# random-keypad-door-controller-flanged-v0.net
KiCad netlist of a schematic drawn in EAGLE
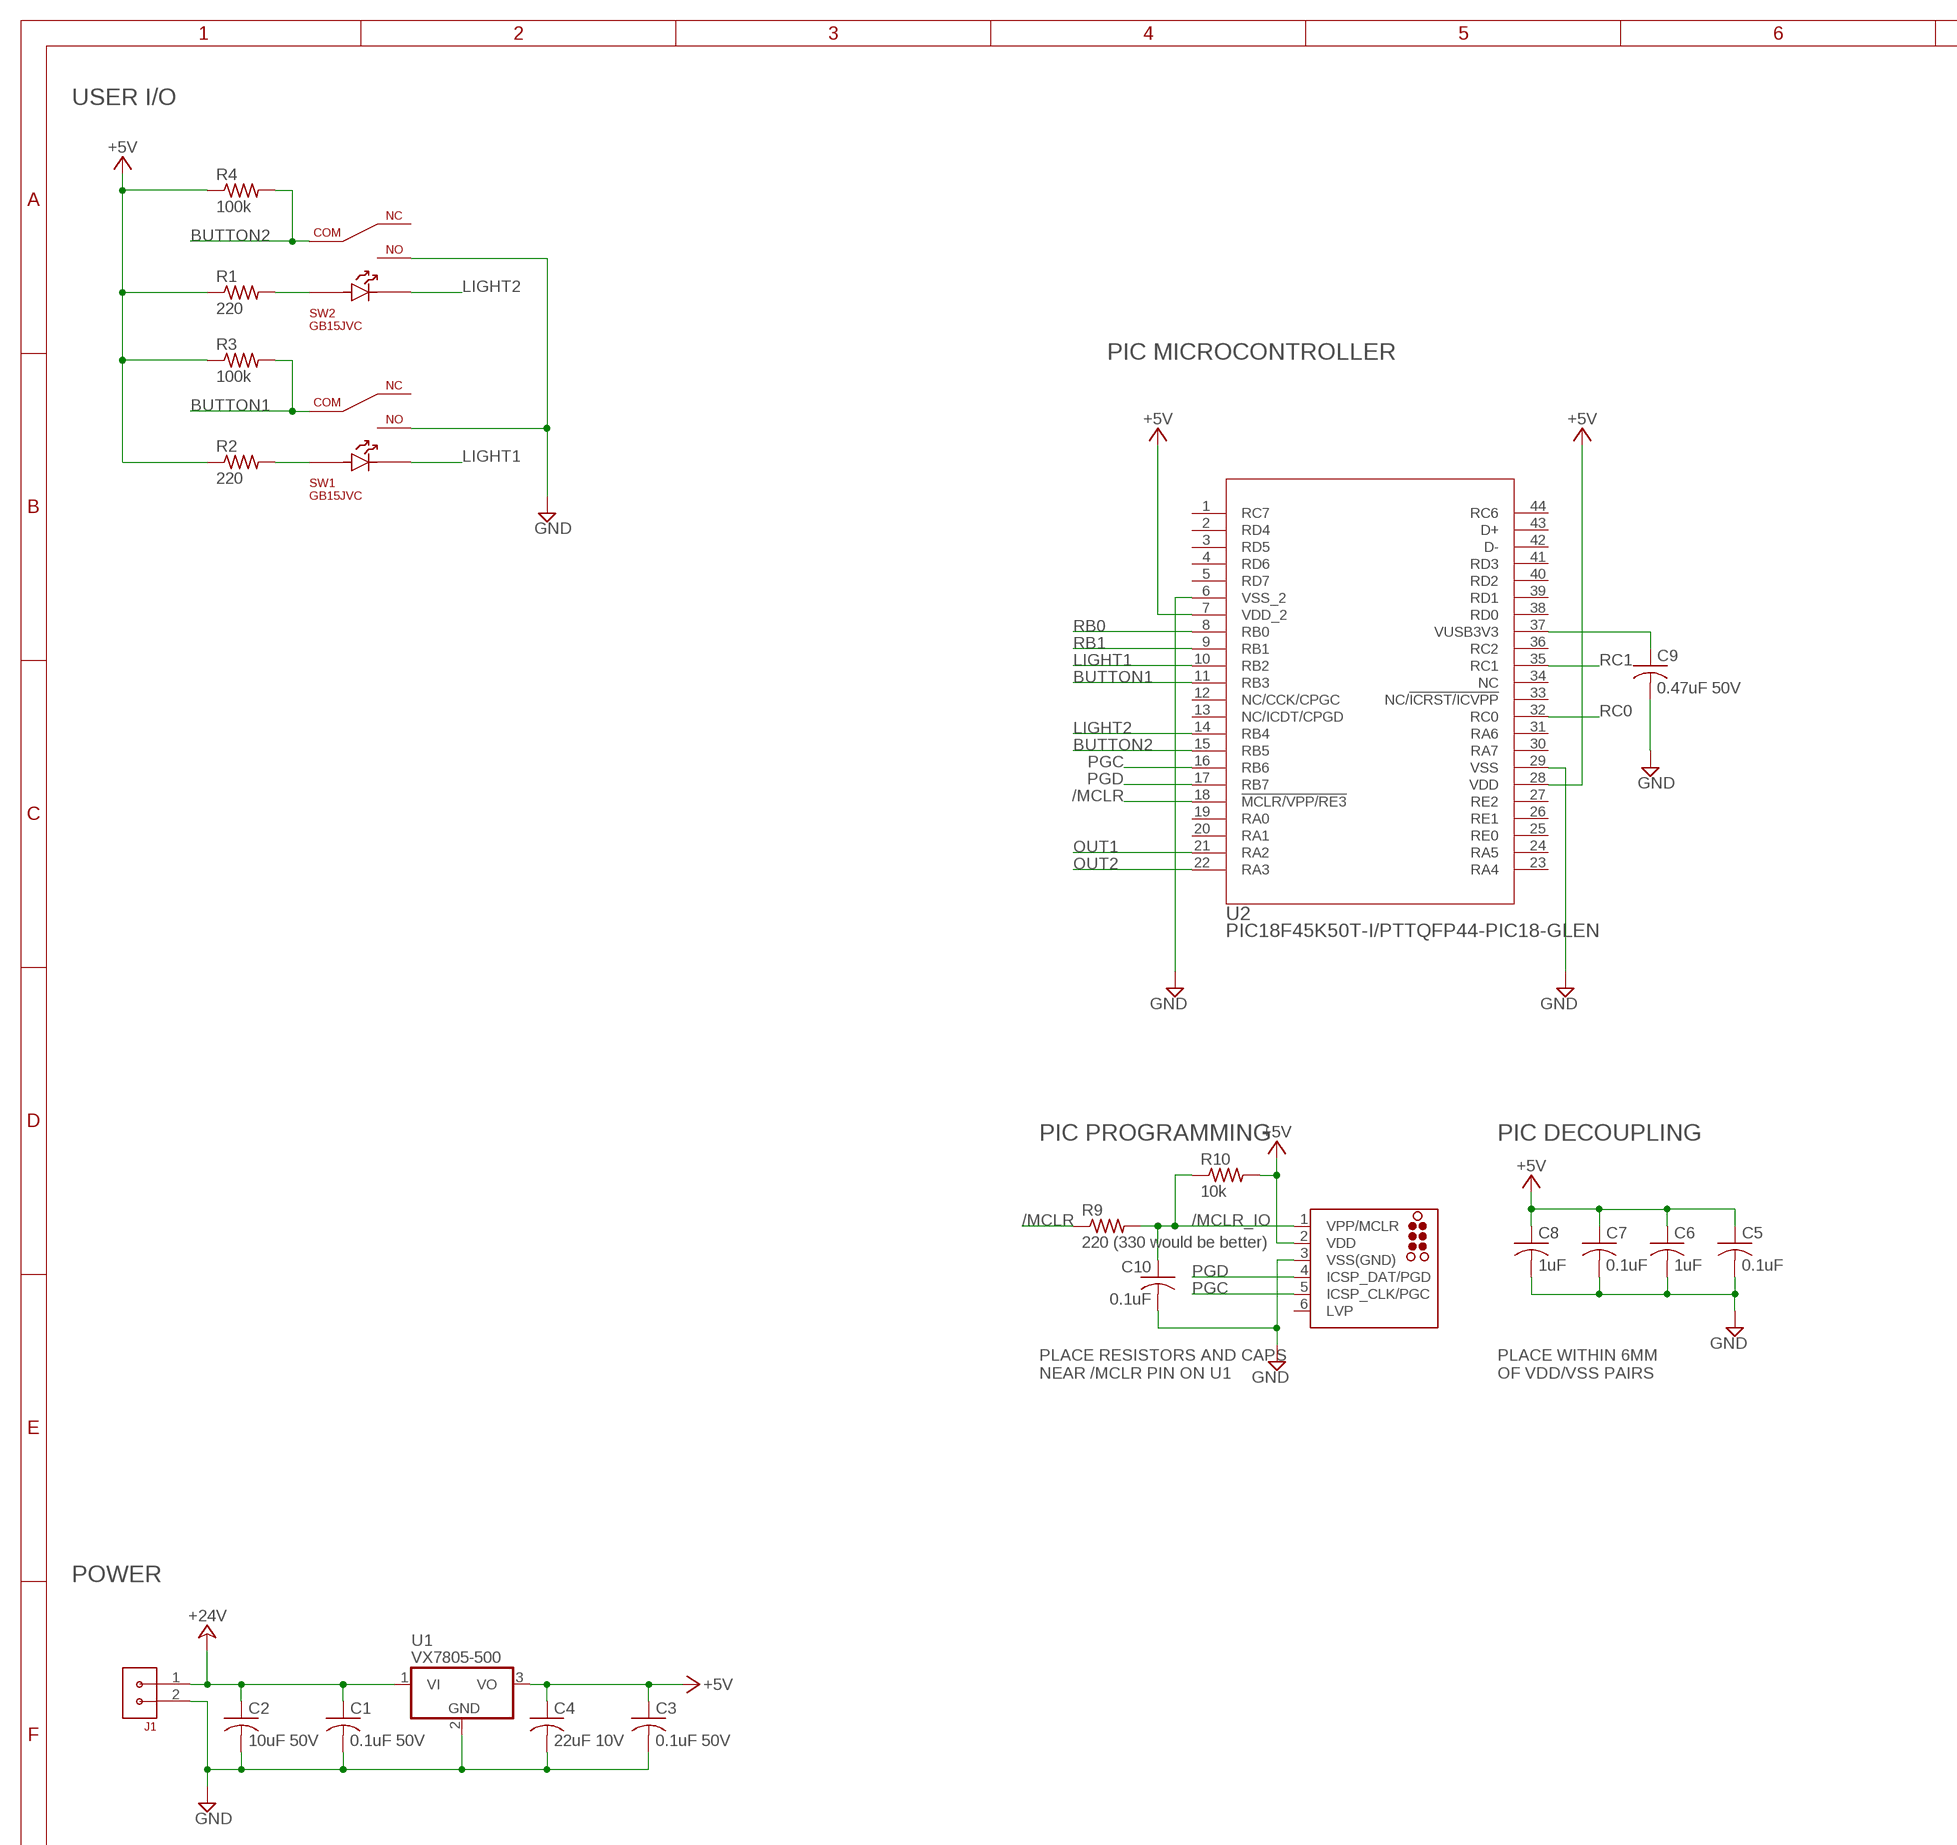
[diagram p0: schematic, sheet 1, part 1 of 2]
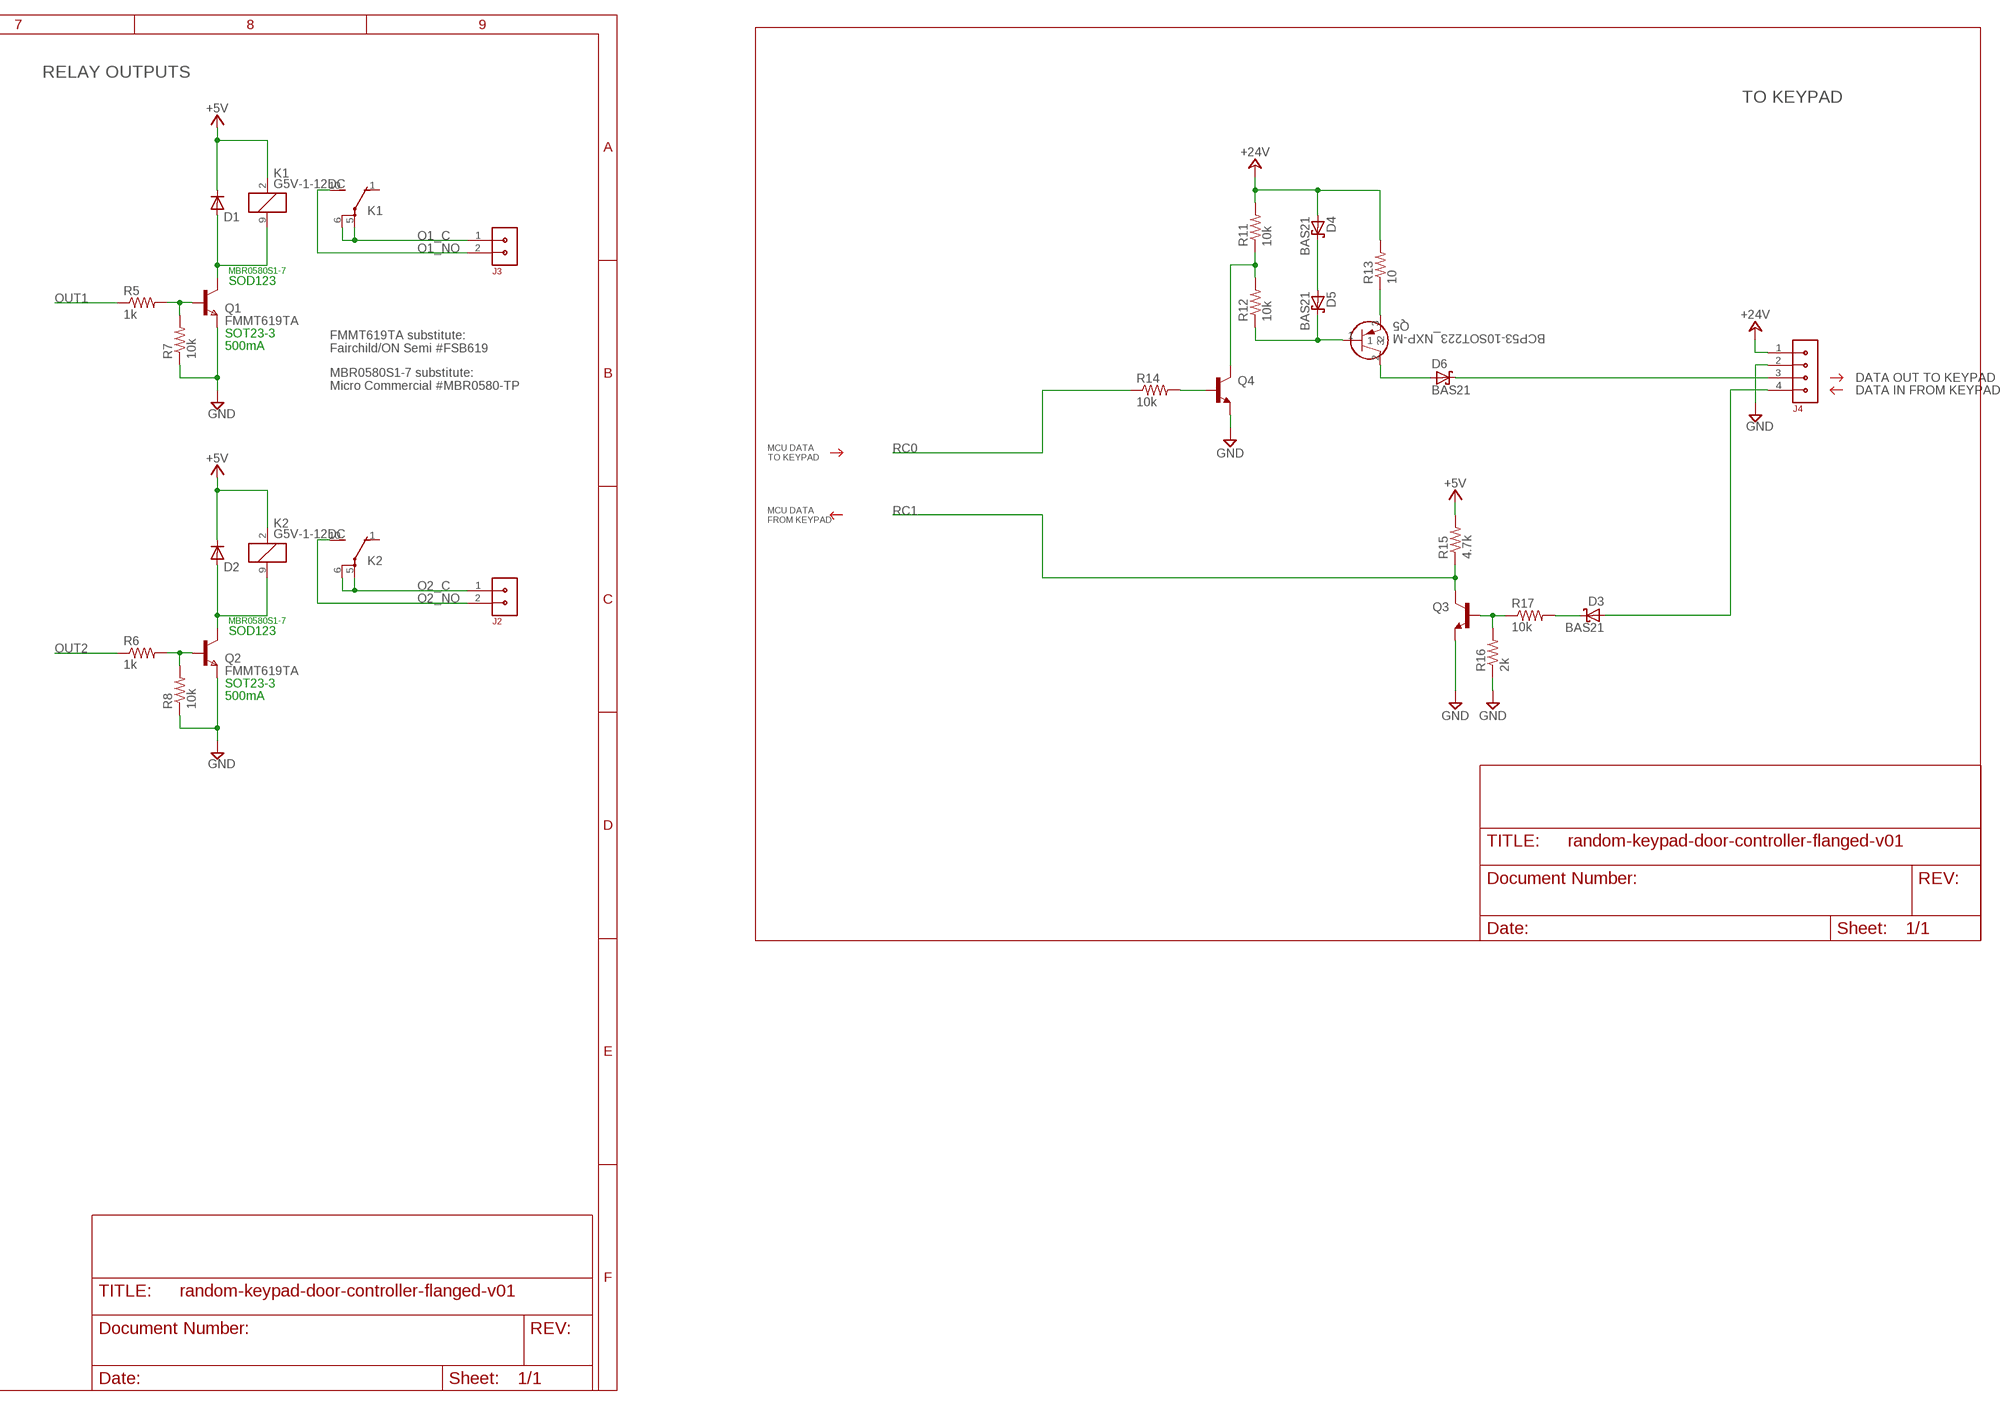
[diagram p1: schematic, sheet 1, part 2 of 2]

(export (version "E")
  (design (tool "Eeschema 10.0.6"))
  (components
    (comp (ref "C1")
      (value "0.1uF 50V")
      (footprint "eagle-import:C1206K")
      (fields (field (name "MFR") "KEMET") (field (name "MFR_PART_NO") "C1206S104M5RACTU"))
      (libsource (lib "eagle-import") (part "C-USC1206K"))
    )
    (comp (ref "C2")
      (value "10uF 50V")
      (footprint "eagle-import:C1210K")
      (fields (field (name "MFR") "KEMET") (field (name "MFR_PART_NO") "C1210C106K5RACTU"))
      (libsource (lib "eagle-import") (part "C-USC1210K"))
    )
    (comp (ref "C3")
      (value "0.1uF 50V")
      (footprint "eagle-import:C1206K")
      (fields (field (name "MFR") "KEMET") (field (name "MFR_PART_NO") "C1206S104M5RACTU"))
      (libsource (lib "eagle-import") (part "C-USC1206K"))
    )
    (comp (ref "C4")
      (value "22uF 10V")
      (footprint "eagle-import:C1206K")
      (fields (field (name "MFR") "KEMET") (field (name "MFR_PART_NO") "C1206C226K8RAC7800"))
      (libsource (lib "eagle-import") (part "C-USC1206K"))
    )
    (comp (ref "C5")
      (value "0.1uF")
      (footprint "eagle-import:C0603K")
      (libsource (lib "eagle-import") (part "C-USC0603K"))
    )
    (comp (ref "C6")
      (value "1uF")
      (footprint "eagle-import:C0603K")
      (libsource (lib "eagle-import") (part "C-USC0603K"))
    )
    (comp (ref "C7")
      (value "0.1uF")
      (footprint "eagle-import:C0603K")
      (libsource (lib "eagle-import") (part "C-USC0603K"))
    )
    (comp (ref "C8")
      (value "1uF")
      (footprint "eagle-import:C0603K")
      (libsource (lib "eagle-import") (part "C-USC0603K"))
    )
    (comp (ref "C9")
      (value "0.47uF 50V")
      (footprint "eagle-import:C1206K")
      (fields (field (name "MFR") "KEMET") (field (name "MFR_PART_NO") "C1206C474K5RACTU"))
      (libsource (lib "eagle-import") (part "C-USC1206K"))
    )
    (comp (ref "C10")
      (value "0.1uF")
      (footprint "eagle-import:C0603K")
      (libsource (lib "eagle-import") (part "C-USC0603K"))
    )
    (comp (ref "D1")
      (value "1N4148W-TP")
      (footprint "eagle-import:SOD123")
      (fields (field (name "MFR") "DIODES INC") (field (name "MFR_PART_NO") "MBR0580S1-7"))
      (libsource (lib "eagle-import") (part "DIODE-SOD123"))
    )
    (comp (ref "D2")
      (value "1N4148W-TP")
      (footprint "eagle-import:SOD123")
      (fields (field (name "MFR") "DIODES INC") (field (name "MFR_PART_NO") "MBR0580S1-7"))
      (libsource (lib "eagle-import") (part "DIODE-SOD123"))
    )
    (comp (ref "D3")
      (value "BAS21")
      (footprint "eagle-import:SOT23")
      (libsource (lib "eagle-import") (part "BAS40"))
    )
    (comp (ref "D4")
      (value "BAS21")
      (footprint "eagle-import:SOT23")
      (libsource (lib "eagle-import") (part "BAS40"))
    )
    (comp (ref "D5")
      (value "BAS21")
      (footprint "eagle-import:SOT23")
      (libsource (lib "eagle-import") (part "BAS40"))
    )
    (comp (ref "D6")
      (value "BAS21")
      (footprint "eagle-import:SOT23")
      (libsource (lib "eagle-import") (part "BAS40"))
    )
    (comp (ref "DEBUG")
      (value "TC2030-MCP-NL")
      (footprint "eagle-import:TC2030-MCP-NL")
      (libsource (lib "eagle-import") (part "TC2030-MCP-NL"))
    )
    (comp (ref "J1")
      (value "CON-3.81MM-1X2-PHOENIX")
      (footprint "eagle-import:CON-PHOENIX-3.81-1X2-RA")
      (libsource (lib "eagle-import") (part "CON-3.81MM-1X2-PHOENIX"))
    )
    (comp (ref "J2")
      (value "CON-3.81MM-1X2-PHOENIX")
      (footprint "eagle-import:CON-PHOENIX-3.81-1X2-RA")
      (libsource (lib "eagle-import") (part "CON-3.81MM-1X2-PHOENIX"))
    )
    (comp (ref "J3")
      (value "CON-3.81MM-1X2-PHOENIX")
      (footprint "eagle-import:CON-PHOENIX-3.81-1X2-RA")
      (libsource (lib "eagle-import") (part "CON-3.81MM-1X2-PHOENIX"))
    )
    (comp (ref "J4")
      (value "CON-3.81MM-1X4-PHOENIX-1803293")
      (footprint "eagle-import:CON-PHOENIX-1803293-3.81-1X4")
      (libsource (lib "eagle-import") (part "CON-3.81MM-1X4-PHOENIX-1803293"))
    )
    (comp (ref "K1")
      (value "G5V-1-12DC")
      (footprint "eagle-import:G5V1")
      (fields
        (field (name "MPN") "G5V-1-DC24")
        (field (name "MFR") "OMRON")
        (field (name "MFR_PART_NO") "G5V-1-DC5")
      )
      (libsource (lib "eagle-import") (part "G5V1"))
    )
    (comp (ref "K2")
      (value "G5V-1-12DC")
      (footprint "eagle-import:G5V1")
      (fields
        (field (name "MPN") "G5V-1-DC24")
        (field (name "MFR") "OMRON")
        (field (name "MFR_PART_NO") "G5V-1-DC5")
      )
      (libsource (lib "eagle-import") (part "G5V1"))
    )
    (comp (ref "Q1")
      (value "FMMT619TA")
      (footprint "eagle-import:SOT-23")
      (fields (field (name "MPN") "DSS20201L-7") (field (name "MFR") "DIODES INC"))
      (libsource (lib "eagle-import") (part "NPNSOT23"))
    )
    (comp (ref "Q2")
      (value "FMMT619TA")
      (footprint "eagle-import:SOT-23")
      (fields (field (name "MPN") "DSS20201L-7") (field (name "MFR") "DIODES INC"))
      (libsource (lib "eagle-import") (part "NPNSOT23"))
    )
    (comp (ref "Q3")
      (value "BC817-40-NPN-SOT23-BEC")
      (footprint "eagle-import:SOT23-BEC")
      (libsource (lib "eagle-import") (part "-NPN-SOT23-BECBC817-40"))
    )
    (comp (ref "Q4")
      (value "BC817-40-NPN-SOT23-BEC")
      (footprint "eagle-import:SOT23-BEC")
      (libsource (lib "eagle-import") (part "-NPN-SOT23-BECBC817-40"))
    )
    (comp (ref "Q5")
      (value "BCP53-10SOT223_NXP-M")
      (footprint "eagle-import:SOT223_NXP-M")
      (fields
        (field (name "MANUFACTURER_PART_NUMBER") "BCP53-10")
        (field (name "COPYRIGHT") "Copyright (C) 2021 Ultra Librarian. All rights reserved.")
      )
      (libsource (lib "eagle-import") (part "BCP53-10SOT223_NXP-M"))
    )
    (comp (ref "R1")
      (value "220")
      (footprint "eagle-import:R0603")
      (libsource (lib "eagle-import") (part "R-US_R0603"))
    )
    (comp (ref "R2")
      (value "220")
      (footprint "eagle-import:R0603")
      (libsource (lib "eagle-import") (part "R-US_R0603"))
    )
    (comp (ref "R3")
      (value "100k")
      (footprint "eagle-import:R0603")
      (libsource (lib "eagle-import") (part "R-US_R0603"))
    )
    (comp (ref "R4")
      (value "100k")
      (footprint "eagle-import:R0603")
      (libsource (lib "eagle-import") (part "R-US_R0603"))
    )
    (comp (ref "R5")
      (value "1k")
      (footprint "eagle-import:R0603")
      (fields (field (name "MFR") "BOURNS") (field (name "MFR_PART_NO") "CR1206-JW-102ELF"))
      (libsource (lib "eagle-import") (part "R-US_R0603"))
    )
    (comp (ref "R6")
      (value "1k")
      (footprint "eagle-import:R0603")
      (fields (field (name "MFR") "BOURNS") (field (name "MFR_PART_NO") "CR1206-JW-102ELF"))
      (libsource (lib "eagle-import") (part "R-US_R0603"))
    )
    (comp (ref "R7")
      (value "10k")
      (footprint "eagle-import:R0603")
      (fields (field (name "MFR") "BOURNS") (field (name "MFR_PART_NO") "CR1206-JW-102ELF"))
      (libsource (lib "eagle-import") (part "R-US_R0603"))
    )
    (comp (ref "R8")
      (value "10k")
      (footprint "eagle-import:R0603")
      (fields (field (name "MFR") "BOURNS") (field (name "MFR_PART_NO") "CR1206-JW-102ELF"))
      (libsource (lib "eagle-import") (part "R-US_R0603"))
    )
    (comp (ref "R9")
      (value "220 (330 would be better)")
      (footprint "eagle-import:R0603")
      (libsource (lib "eagle-import") (part "R-US_R0603"))
    )
    (comp (ref "R10")
      (value "10k")
      (footprint "eagle-import:R0603")
      (libsource (lib "eagle-import") (part "R-US_R0603"))
    )
    (comp (ref "R11")
      (value "10k")
      (footprint "eagle-import:R0603")
      (libsource (lib "eagle-import") (part "resistor_R-US_R0603"))
    )
    (comp (ref "R12")
      (value "10k")
      (footprint "eagle-import:R0603")
      (libsource (lib "eagle-import") (part "resistor_R-US_R0603"))
    )
    (comp (ref "R13")
      (value "10")
      (footprint "eagle-import:R0603")
      (libsource (lib "eagle-import") (part "resistor_R-US_R0603"))
    )
    (comp (ref "R14")
      (value "10k")
      (footprint "eagle-import:R0603")
      (libsource (lib "eagle-import") (part "resistor_R-US_R0603"))
    )
    (comp (ref "R15")
      (value "4.7k")
      (footprint "eagle-import:R0603")
      (libsource (lib "eagle-import") (part "resistor_R-US_R0603"))
    )
    (comp (ref "R16")
      (value "2k")
      (footprint "eagle-import:R0603")
      (libsource (lib "eagle-import") (part "resistor_R-US_R0603"))
    )
    (comp (ref "R17")
      (value "10k")
      (footprint "eagle-import:R0603")
      (libsource (lib "eagle-import") (part "resistor_R-US_R0603"))
    )
    (comp (ref "SW1")
      (value "GB15JVC")
      (footprint "eagle-import:GB15JHC")
      (libsource (lib "eagle-import") (part "GB15JHC"))
    )
    (comp (ref "SW2")
      (value "GB15JVC")
      (footprint "eagle-import:GB15JHC")
      (libsource (lib "eagle-import") (part "GB15JHC"))
    )
    (comp (ref "U1")
      (value "VX7805-500")
      (footprint "eagle-import:CUI-78XX-500")
      (libsource (lib "eagle-import") (part "CUI-V7803-500"))
    )
    (comp (ref "U2")
      (value "PIC18F45K50T-I/PTTQFP44-PIC18-GLEN")
      (footprint "eagle-import:TQFP44-PIC18-GLEN")
      (libsource (lib "eagle-import") (part "PIC18F45K50T-I/PTTQFP44-PIC18-GLEN"))
    )
  )
  (nets
    (net (code "1") (name "+5V") (class "Default")
      (node (ref "C3") (pin "1") (pinfunction "1_1") (pintype "passive"))
      (node (ref "C4") (pin "1") (pinfunction "1_1") (pintype "passive"))
      (node (ref "C5") (pin "1") (pinfunction "1_1") (pintype "passive"))
      (node (ref "C6") (pin "1") (pinfunction "1_1") (pintype "passive"))
      (node (ref "C7") (pin "1") (pinfunction "1_1") (pintype "passive"))
      (node (ref "C8") (pin "1") (pinfunction "1_1") (pintype "passive"))
      (node (ref "D1") (pin "C") (pinfunction "C_C") (pintype "passive"))
      (node (ref "D2") (pin "C") (pinfunction "C_C") (pintype "passive"))
      (node (ref "DEBUG") (pin "2") (pinfunction "VDD_2") (pintype "power_in"))
      (node (ref "K1") (pin "2") (pinfunction "1_2") (pintype "passive"))
      (node (ref "K2") (pin "2") (pinfunction "1_2") (pintype "passive"))
      (node (ref "R1") (pin "1") (pinfunction "1_1") (pintype "passive"))
      (node (ref "R10") (pin "2") (pinfunction "2_2") (pintype "passive"))
      (node (ref "R15") (pin "2") (pinfunction "2_2") (pintype "passive"))
      (node (ref "R2") (pin "1") (pinfunction "1_1") (pintype "passive"))
      (node (ref "R3") (pin "1") (pinfunction "1_1") (pintype "passive"))
      (node (ref "R4") (pin "1") (pinfunction "1_1") (pintype "passive"))
      (node (ref "U1") (pin "3") (pinfunction "VO_3") (pintype "passive"))
      (node (ref "U2") (pin "28") (pinfunction "VDD_28") (pintype "power_in"))
      (node (ref "U2") (pin "7") (pinfunction "VDD_2_7") (pintype "power_in"))
    )
    (net (code "2") (name "+24V") (class "Default")
      (node (ref "C1") (pin "1") (pinfunction "1_1") (pintype "passive"))
      (node (ref "C2") (pin "1") (pinfunction "1_1") (pintype "passive"))
      (node (ref "D4") (pin "1") (pinfunction "A_1") (pintype "passive"))
      (node (ref "J1") (pin "1") (pinfunction "1_1") (pintype "bidirectional"))
      (node (ref "J4") (pin "1") (pinfunction "1_1") (pintype "bidirectional"))
      (node (ref "R11") (pin "2") (pinfunction "2_2") (pintype "passive"))
      (node (ref "R13") (pin "2") (pinfunction "2_2") (pintype "passive"))
      (node (ref "U1") (pin "1") (pinfunction "VI_1") (pintype "input"))
    )
    (net (code "3") (name "/BUTTON1") (class "Default")
      (node (ref "R3") (pin "2") (pinfunction "2_2") (pintype "passive"))
      (node (ref "SW1") (pin "5") (pinfunction "5_5") (pintype "bidirectional"))
      (node (ref "U2") (pin "11") (pinfunction "RB3_11") (pintype "bidirectional"))
    )
    (net (code "4") (name "/BUTTON2") (class "Default")
      (node (ref "R4") (pin "2") (pinfunction "2_2") (pintype "passive"))
      (node (ref "SW2") (pin "5") (pinfunction "5_5") (pintype "bidirectional"))
      (node (ref "U2") (pin "15") (pinfunction "RB5_15") (pintype "bidirectional"))
    )
    (net (code "5") (name "/LIGHT1") (class "Default")
      (node (ref "SW1") (pin "3") (pinfunction "3_3") (pintype "bidirectional"))
      (node (ref "U2") (pin "10") (pinfunction "RB2_10") (pintype "bidirectional"))
    )
    (net (code "6") (name "/LIGHT2") (class "Default")
      (node (ref "SW2") (pin "3") (pinfunction "3_3") (pintype "bidirectional"))
      (node (ref "U2") (pin "14") (pinfunction "RB4_14") (pintype "bidirectional"))
    )
    (net (code "7") (name "/O1_C") (class "Default")
      (node (ref "J3") (pin "1") (pinfunction "1_1") (pintype "bidirectional"))
      (node (ref "K1") (pin "5") (pinfunction "P_5") (pintype "passive"))
      (node (ref "K1") (pin "6") (pinfunction "P_6") (pintype "passive"))
    )
    (net (code "8") (name "/O1_NO") (class "Default")
      (node (ref "J3") (pin "2") (pinfunction "2_2") (pintype "bidirectional"))
      (node (ref "K1") (pin "10") (pinfunction "S_10") (pintype "passive"))
    )
    (net (code "9") (name "/O2_C") (class "Default")
      (node (ref "J2") (pin "1") (pinfunction "1_1") (pintype "bidirectional"))
      (node (ref "K2") (pin "5") (pinfunction "P_5") (pintype "passive"))
      (node (ref "K2") (pin "6") (pinfunction "P_6") (pintype "passive"))
    )
    (net (code "10") (name "/O2_NO") (class "Default")
      (node (ref "J2") (pin "2") (pinfunction "2_2") (pintype "bidirectional"))
      (node (ref "K2") (pin "10") (pinfunction "S_10") (pintype "passive"))
    )
    (net (code "11") (name "/OUT1") (class "Default")
      (node (ref "R5") (pin "1") (pinfunction "1_1") (pintype "passive"))
      (node (ref "U2") (pin "21") (pinfunction "RA2_21") (pintype "bidirectional"))
    )
    (net (code "12") (name "/OUT2") (class "Default")
      (node (ref "R6") (pin "1") (pinfunction "1_1") (pintype "passive"))
      (node (ref "U2") (pin "22") (pinfunction "RA3_22") (pintype "bidirectional"))
    )
    (net (code "13") (name "/PGC") (class "Default")
      (node (ref "DEBUG") (pin "5") (pinfunction "ICSP_CLK/PGC_5") (pintype "output"))
      (node (ref "U2") (pin "16") (pinfunction "RB6_16") (pintype "bidirectional"))
    )
    (net (code "14") (name "/PGD") (class "Default")
      (node (ref "DEBUG") (pin "4") (pinfunction "ICSP_DAT/PGD_4") (pintype "bidirectional"))
      (node (ref "U2") (pin "17") (pinfunction "RB7_17") (pintype "bidirectional"))
    )
    (net (code "15") (name "/RB0") (class "Default")
      (node (ref "U2") (pin "8") (pinfunction "RB0_8") (pintype "bidirectional"))
    )
    (net (code "16") (name "/RB1") (class "Default")
      (node (ref "U2") (pin "9") (pinfunction "RB1_9") (pintype "bidirectional"))
    )
    (net (code "17") (name "/RC0") (class "Default")
      (node (ref "R14") (pin "1") (pinfunction "1_1") (pintype "passive"))
      (node (ref "U2") (pin "32") (pinfunction "RC0_32") (pintype "bidirectional"))
    )
    (net (code "18") (name "/RC1") (class "Default")
      (node (ref "Q3") (pin "C") (pinfunction "C_C") (pintype "passive"))
      (node (ref "R15") (pin "1") (pinfunction "1_1") (pintype "passive"))
      (node (ref "U2") (pin "35") (pinfunction "RC1_35") (pintype "bidirectional"))
    )
    (net (code "19") (name "/{slash}MCLR") (class "Default")
      (node (ref "R9") (pin "1") (pinfunction "1_1") (pintype "passive"))
      (node (ref "U2") (pin "18") (pinfunction "~{MCLR/VPP/RE3}_18") (pintype "bidirectional"))
    )
    (net (code "20") (name "/{slash}MCLR_IO") (class "Default")
      (node (ref "C10") (pin "1") (pinfunction "1_1") (pintype "passive"))
      (node (ref "DEBUG") (pin "1") (pinfunction "VPP/MCLR_1") (pintype "passive"))
      (node (ref "R10") (pin "1") (pinfunction "1_1") (pintype "passive"))
      (node (ref "R9") (pin "2") (pinfunction "2_2") (pintype "passive"))
    )
    (net (code "21") (name "GND") (class "Default")
      (node (ref "C1") (pin "2") (pinfunction "2_2") (pintype "passive"))
      (node (ref "C10") (pin "2") (pinfunction "2_2") (pintype "passive"))
      (node (ref "C2") (pin "2") (pinfunction "2_2") (pintype "passive"))
      (node (ref "C3") (pin "2") (pinfunction "2_2") (pintype "passive"))
      (node (ref "C4") (pin "2") (pinfunction "2_2") (pintype "passive"))
      (node (ref "C5") (pin "2") (pinfunction "2_2") (pintype "passive"))
      (node (ref "C6") (pin "2") (pinfunction "2_2") (pintype "passive"))
      (node (ref "C7") (pin "2") (pinfunction "2_2") (pintype "passive"))
      (node (ref "C8") (pin "2") (pinfunction "2_2") (pintype "passive"))
      (node (ref "C9") (pin "2") (pinfunction "2_2") (pintype "passive"))
      (node (ref "DEBUG") (pin "3") (pinfunction "VSS(GND)_3") (pintype "power_in"))
      (node (ref "J1") (pin "2") (pinfunction "2_2") (pintype "bidirectional"))
      (node (ref "J4") (pin "2") (pinfunction "2_2") (pintype "bidirectional"))
      (node (ref "Q1") (pin "2") (pinfunction "E_2") (pintype "passive"))
      (node (ref "Q2") (pin "2") (pinfunction "E_2") (pintype "passive"))
      (node (ref "Q3") (pin "E") (pinfunction "E_E") (pintype "passive"))
      (node (ref "Q4") (pin "E") (pinfunction "E_E") (pintype "passive"))
      (node (ref "R16") (pin "1") (pinfunction "1_1") (pintype "passive"))
      (node (ref "R7") (pin "1") (pinfunction "1_1") (pintype "passive"))
      (node (ref "R8") (pin "1") (pinfunction "1_1") (pintype "passive"))
      (node (ref "SW1") (pin "4") (pinfunction "4_4") (pintype "bidirectional"))
      (node (ref "SW2") (pin "4") (pinfunction "4_4") (pintype "bidirectional"))
      (node (ref "U1") (pin "2") (pinfunction "GND_2") (pintype "passive"))
      (node (ref "U2") (pin "29") (pinfunction "VSS_29") (pintype "power_in"))
      (node (ref "U2") (pin "6") (pinfunction "VSS_2_6") (pintype "power_in"))
    )
    (net (code "22") (name "Net-(D3-A)") (class "Default")
      (node (ref "D3") (pin "1") (pinfunction "A_1") (pintype "passive"))
      (node (ref "J4") (pin "4") (pinfunction "4_4") (pintype "bidirectional"))
    )
    (net (code "23") (name "Net-(D3-C)") (class "Default")
      (node (ref "D3") (pin "3") (pinfunction "C_3") (pintype "passive"))
      (node (ref "R17") (pin "2") (pinfunction "2_2") (pintype "passive"))
    )
    (net (code "24") (name "Net-(D4-C)") (class "Default")
      (node (ref "D4") (pin "3") (pinfunction "C_3") (pintype "passive"))
      (node (ref "D5") (pin "1") (pinfunction "A_1") (pintype "passive"))
    )
    (net (code "25") (name "Net-(D5-C)") (class "Default")
      (node (ref "D5") (pin "3") (pinfunction "C_3") (pintype "passive"))
      (node (ref "Q5") (pin "1") (pinfunction "1_1") (pintype "passive"))
      (node (ref "R12") (pin "1") (pinfunction "1_1") (pintype "passive"))
    )
    (net (code "26") (name "Net-(D6-A)") (class "Default")
      (node (ref "D6") (pin "1") (pinfunction "A_1") (pintype "passive"))
      (node (ref "Q5") (pin "2") (pinfunction "2_2") (pintype "passive"))
    )
    (net (code "27") (name "Net-(D6-C)") (class "Default")
      (node (ref "D6") (pin "3") (pinfunction "C_3") (pintype "passive"))
      (node (ref "J4") (pin "3") (pinfunction "3_3") (pintype "bidirectional"))
    )
    (net (code "28") (name "Net-(K1A-2)") (class "Default")
      (node (ref "D1") (pin "A") (pinfunction "A_A") (pintype "passive"))
      (node (ref "K1") (pin "9") (pinfunction "2_9") (pintype "passive"))
      (node (ref "Q1") (pin "1") (pinfunction "C_1") (pintype "passive"))
    )
    (net (code "29") (name "Net-(K2A-2)") (class "Default")
      (node (ref "D2") (pin "A") (pinfunction "A_A") (pintype "passive"))
      (node (ref "K2") (pin "9") (pinfunction "2_9") (pintype "passive"))
      (node (ref "Q2") (pin "1") (pinfunction "C_1") (pintype "passive"))
    )
    (net (code "30") (name "Net-(Q1-B)") (class "Default")
      (node (ref "Q1") (pin "3") (pinfunction "B_3") (pintype "passive"))
      (node (ref "R5") (pin "2") (pinfunction "2_2") (pintype "passive"))
      (node (ref "R7") (pin "2") (pinfunction "2_2") (pintype "passive"))
    )
    (net (code "31") (name "Net-(Q2-B)") (class "Default")
      (node (ref "Q2") (pin "3") (pinfunction "B_3") (pintype "passive"))
      (node (ref "R6") (pin "2") (pinfunction "2_2") (pintype "passive"))
      (node (ref "R8") (pin "2") (pinfunction "2_2") (pintype "passive"))
    )
    (net (code "32") (name "Net-(Q3-PadB)") (class "Default")
      (node (ref "Q3") (pin "B") (pinfunction "B_B") (pintype "passive"))
      (node (ref "R16") (pin "2") (pinfunction "2_2") (pintype "passive"))
      (node (ref "R17") (pin "1") (pinfunction "1_1") (pintype "passive"))
    )
    (net (code "33") (name "Net-(Q4-PadB)") (class "Default")
      (node (ref "Q4") (pin "B") (pinfunction "B_B") (pintype "passive"))
      (node (ref "R14") (pin "2") (pinfunction "2_2") (pintype "passive"))
    )
    (net (code "34") (name "Net-(Q4-PadC)") (class "Default")
      (node (ref "Q4") (pin "C") (pinfunction "C_C") (pintype "passive"))
      (node (ref "R11") (pin "1") (pinfunction "1_1") (pintype "passive"))
      (node (ref "R12") (pin "2") (pinfunction "2_2") (pintype "passive"))
    )
    (net (code "35") (name "Net-(Q5-Pad3)") (class "Default")
      (node (ref "Q5") (pin "3") (pinfunction "3_3") (pintype "passive"))
      (node (ref "R13") (pin "1") (pinfunction "1_1") (pintype "passive"))
    )
    (net (code "36") (name "Net-(R1-Pad2)") (class "Default")
      (node (ref "R1") (pin "2") (pinfunction "2_2") (pintype "passive"))
      (node (ref "SW2") (pin "1") (pinfunction "1_1") (pintype "bidirectional"))
    )
    (net (code "37") (name "Net-(R2-Pad2)") (class "Default")
      (node (ref "R2") (pin "2") (pinfunction "2_2") (pintype "passive"))
      (node (ref "SW1") (pin "1") (pinfunction "1_1") (pintype "bidirectional"))
    )
    (net (code "38") (name "Net-(U2-VUSB3V3)") (class "Default")
      (node (ref "C9") (pin "1") (pinfunction "1_1") (pintype "passive"))
      (node (ref "U2") (pin "37") (pinfunction "VUSB3V3_37") (pintype "power_in"))
    )
    (net (code "39") (name "unconnected-(DEBUG-LVP-Pad6)") (class "Default")
      (node (ref "DEBUG") (pin "6") (pinfunction "LVP_6") (pintype "bidirectional"))
    )
    (net (code "40") (name "unconnected-(K1B-O-Pad1)") (class "Default")
      (node (ref "K1") (pin "1") (pinfunction "O_1") (pintype "passive"))
    )
    (net (code "41") (name "unconnected-(K2B-O-Pad1)") (class "Default")
      (node (ref "K2") (pin "1") (pinfunction "O_1") (pintype "passive"))
    )
    (net (code "42") (name "unconnected-(SW1-Pad6)") (class "Default")
      (node (ref "SW1") (pin "6") (pinfunction "6_6") (pintype "bidirectional"))
    )
    (net (code "43") (name "unconnected-(SW2-Pad6)") (class "Default")
      (node (ref "SW2") (pin "6") (pinfunction "6_6") (pintype "bidirectional"))
    )
    (net (code "44") (name "unconnected-(U2-D+-Pad43)") (class "Default")
      (node (ref "U2") (pin "43") (pinfunction "D+_43") (pintype "passive"))
    )
    (net (code "45") (name "unconnected-(U2-D--Pad42)") (class "Default")
      (node (ref "U2") (pin "42") (pinfunction "D-_42") (pintype "passive"))
    )
    (net (code "46") (name "unconnected-(U2-NC-Pad34)") (class "Default")
      (node (ref "U2") (pin "34") (pinfunction "NC_34") (pintype "no_connect"))
    )
    (net (code "47") (name "unconnected-(U2-NC{slash}CCK{slash}CPGC-Pad12)") (class "Default")
      (node (ref "U2") (pin "12") (pinfunction "NC/CCK/CPGC_12") (pintype "bidirectional"))
    )
    (net (code "48") (name "unconnected-(U2-NC{slash}ICDT{slash}CPGD-Pad13)") (class "Default")
      (node (ref "U2") (pin "13") (pinfunction "NC/ICDT/CPGD_13") (pintype "bidirectional"))
    )
    (net (code "49") (name "unconnected-(U2-NC{slash}~{ICRST{slash}ICVPP}-Pad33)") (class "Default")
      (node (ref "U2") (pin "33") (pinfunction "NC/~{ICRST/ICVPP}_33") (pintype "bidirectional"))
    )
    (net (code "50") (name "unconnected-(U2-RA0-Pad19)") (class "Default")
      (node (ref "U2") (pin "19") (pinfunction "RA0_19") (pintype "bidirectional"))
    )
    (net (code "51") (name "unconnected-(U2-RA1-Pad20)") (class "Default")
      (node (ref "U2") (pin "20") (pinfunction "RA1_20") (pintype "bidirectional"))
    )
    (net (code "52") (name "unconnected-(U2-RA4-Pad23)") (class "Default")
      (node (ref "U2") (pin "23") (pinfunction "RA4_23") (pintype "bidirectional"))
    )
    (net (code "53") (name "unconnected-(U2-RA5-Pad24)") (class "Default")
      (node (ref "U2") (pin "24") (pinfunction "RA5_24") (pintype "bidirectional"))
    )
    (net (code "54") (name "unconnected-(U2-RA6-Pad31)") (class "Default")
      (node (ref "U2") (pin "31") (pinfunction "RA6_31") (pintype "bidirectional"))
    )
    (net (code "55") (name "unconnected-(U2-RA7-Pad30)") (class "Default")
      (node (ref "U2") (pin "30") (pinfunction "RA7_30") (pintype "bidirectional"))
    )
    (net (code "56") (name "unconnected-(U2-RC2-Pad36)") (class "Default")
      (node (ref "U2") (pin "36") (pinfunction "RC2_36") (pintype "bidirectional"))
    )
    (net (code "57") (name "unconnected-(U2-RC6-Pad44)") (class "Default")
      (node (ref "U2") (pin "44") (pinfunction "RC6_44") (pintype "bidirectional"))
    )
    (net (code "58") (name "unconnected-(U2-RC7-Pad1)") (class "Default")
      (node (ref "U2") (pin "1") (pinfunction "RC7_1") (pintype "bidirectional"))
    )
    (net (code "59") (name "unconnected-(U2-RD0-Pad38)") (class "Default")
      (node (ref "U2") (pin "38") (pinfunction "RD0_38") (pintype "bidirectional"))
    )
    (net (code "60") (name "unconnected-(U2-RD1-Pad39)") (class "Default")
      (node (ref "U2") (pin "39") (pinfunction "RD1_39") (pintype "bidirectional"))
    )
    (net (code "61") (name "unconnected-(U2-RD2-Pad40)") (class "Default")
      (node (ref "U2") (pin "40") (pinfunction "RD2_40") (pintype "bidirectional"))
    )
    (net (code "62") (name "unconnected-(U2-RD3-Pad41)") (class "Default")
      (node (ref "U2") (pin "41") (pinfunction "RD3_41") (pintype "bidirectional"))
    )
    (net (code "63") (name "unconnected-(U2-RD4-Pad2)") (class "Default")
      (node (ref "U2") (pin "2") (pinfunction "RD4_2") (pintype "bidirectional"))
    )
    (net (code "64") (name "unconnected-(U2-RD5-Pad3)") (class "Default")
      (node (ref "U2") (pin "3") (pinfunction "RD5_3") (pintype "bidirectional"))
    )
    (net (code "65") (name "unconnected-(U2-RD6-Pad4)") (class "Default")
      (node (ref "U2") (pin "4") (pinfunction "RD6_4") (pintype "bidirectional"))
    )
    (net (code "66") (name "unconnected-(U2-RD7-Pad5)") (class "Default")
      (node (ref "U2") (pin "5") (pinfunction "RD7_5") (pintype "bidirectional"))
    )
    (net (code "67") (name "unconnected-(U2-RE0-Pad25)") (class "Default")
      (node (ref "U2") (pin "25") (pinfunction "RE0_25") (pintype "bidirectional"))
    )
    (net (code "68") (name "unconnected-(U2-RE1-Pad26)") (class "Default")
      (node (ref "U2") (pin "26") (pinfunction "RE1_26") (pintype "bidirectional"))
    )
    (net (code "69") (name "unconnected-(U2-RE2-Pad27)") (class "Default")
      (node (ref "U2") (pin "27") (pinfunction "RE2_27") (pintype "bidirectional"))
    )
  )
)
